# Programming_Interface_and_Power.net
KiCad netlist of a schematic drawn in Altium Designer
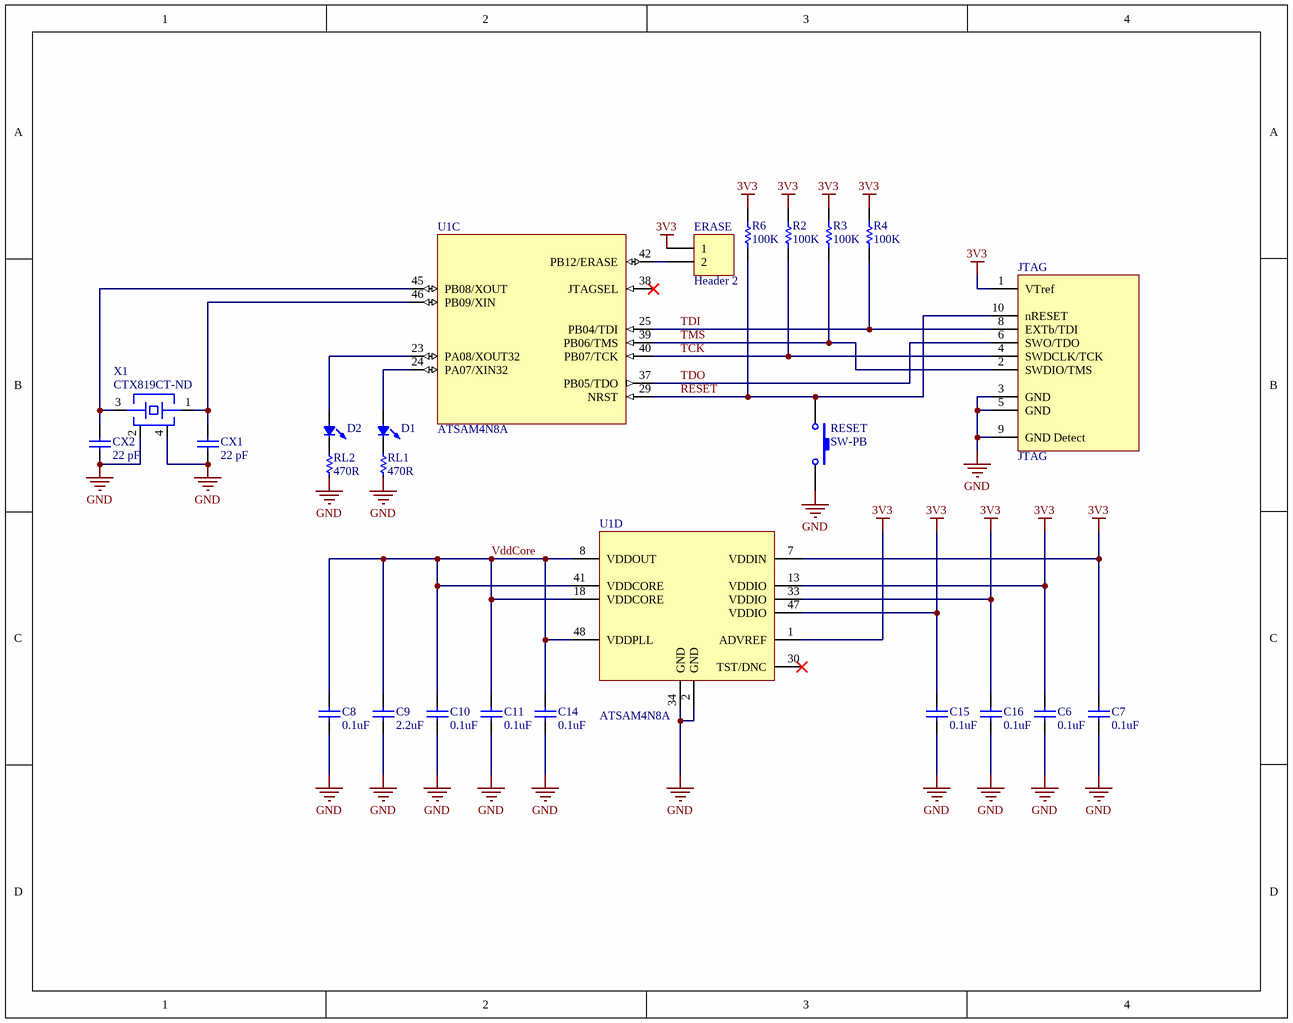
[diagram p0: Programming Interface and Power.SchDoc]

(export (version "E")
  (design (tool "Eeschema 10.0.6"))
  (components
    (comp (ref "C6")
      (value "0.1uF")
      (footprint "0603C")
      (description "Capacitor (Semiconductor SIM Model)")
      (fields (field (name "Comment") "Cap Semi") (field (name "PUBLISHER") "Altium Limited"))
      (libsource (lib "Miscellaneous Devices") (part "Cap Semi"))
    )
    (comp (ref "C7")
      (value "0.1uF")
      (footprint "0603C")
      (description "Capacitor (Semiconductor SIM Model)")
      (fields (field (name "Comment") "Cap Semi") (field (name "PUBLISHER") "Altium Limited"))
      (libsource (lib "Miscellaneous Devices") (part "Cap Semi"))
    )
    (comp (ref "C8")
      (value "0.1uF")
      (footprint "0603C")
      (description "Capacitor (Semiconductor SIM Model)")
      (fields (field (name "Comment") "Cap Semi") (field (name "PUBLISHER") "Altium Limited"))
      (libsource (lib "Miscellaneous Devices") (part "Cap Semi"))
    )
    (comp (ref "C9")
      (value "2.2uF")
      (footprint "1206C")
      (description "Capacitor (Semiconductor SIM Model)")
      (fields (field (name "Comment") "Cap Semi") (field (name "PUBLISHER") "Altium Limited"))
      (libsource (lib "Miscellaneous Devices") (part "Cap Semi"))
    )
    (comp (ref "C10")
      (value "0.1uF")
      (footprint "0603C")
      (description "Capacitor (Semiconductor SIM Model)")
      (fields (field (name "Comment") "Cap Semi") (field (name "PUBLISHER") "Altium Limited"))
      (libsource (lib "Miscellaneous Devices") (part "Cap Semi"))
    )
    (comp (ref "C11")
      (value "0.1uF")
      (footprint "0603C")
      (description "Capacitor (Semiconductor SIM Model)")
      (fields (field (name "Comment") "Cap Semi") (field (name "PUBLISHER") "Altium Limited"))
      (libsource (lib "Miscellaneous Devices") (part "Cap Semi"))
    )
    (comp (ref "C14")
      (value "0.1uF")
      (footprint "0603C")
      (description "Capacitor (Semiconductor SIM Model)")
      (fields (field (name "Comment") "Cap Semi") (field (name "PUBLISHER") "Altium Limited"))
      (libsource (lib "Miscellaneous Devices") (part "Cap Semi"))
    )
    (comp (ref "C15")
      (value "0.1uF")
      (footprint "0603C")
      (description "Capacitor (Semiconductor SIM Model)")
      (fields (field (name "Comment") "Cap Semi") (field (name "PUBLISHER") "Altium Limited"))
      (libsource (lib "Miscellaneous Devices") (part "Cap Semi"))
    )
    (comp (ref "C16")
      (value "0.1uF")
      (footprint "0603C")
      (description "Capacitor (Semiconductor SIM Model)")
      (fields (field (name "Comment") "Cap Semi") (field (name "PUBLISHER") "Altium Limited"))
      (libsource (lib "Miscellaneous Devices") (part "Cap Semi"))
    )
    (comp (ref "CX1")
      (value "22 pF")
      (footprint "0603C")
      (description "Capacitor (Semiconductor SIM Model)")
      (fields (field (name "Comment") "Cap Semi") (field (name "PUBLISHER") "Altium Limited"))
      (libsource (lib "Miscellaneous Devices") (part "Cap Semi"))
    )
    (comp (ref "CX2")
      (value "22 pF")
      (footprint "0603C")
      (description "Capacitor (Semiconductor SIM Model)")
      (fields (field (name "Comment") "Cap Semi") (field (name "PUBLISHER") "Altium Limited"))
      (libsource (lib "Miscellaneous Devices") (part "Cap Semi"))
    )
    (comp (ref "D1")
      (value "LED0")
      (footprint "0603 SMT LED")
      (description "T 1 3/4 LED")
      (fields (field (name "PUBLISHER") "Altium Limited"))
      (libsource (lib "Miscellaneous Devices") (part "LED0"))
    )
    (comp (ref "D2")
      (value "LED0")
      (footprint "0603 SMT LED")
      (description "T 1 3/4 LED")
      (fields (field (name "PUBLISHER") "Altium Limited"))
      (libsource (lib "Miscellaneous Devices") (part "LED0"))
    )
    (comp (ref "ERASE")
      (value "Header 2")
      (footprint "HDR1X2")
      (description "Header, 2-Pin")
      (fields (field (name "PUBLISHER") "Altium Limited"))
      (libsource (lib "Miscellaneous Connectors") (part "Header 2"))
    )
    (comp (ref "JTAG")
      (value "JTAG")
      (footprint "MHDR2X5 - Shrouded")
      (description "ARM 10-Pin JTAG Interface")
      (libsource (lib "Connectors") (part "ARM JTAG-10"))
    )
    (comp (ref "R2")
      (value "100K")
      (footprint "0603R")
      (description "Semiconductor Resistor")
      (fields (field (name "Comment") "Res Semi") (field (name "PUBLISHER") "Altium Limited"))
      (libsource (lib "Miscellaneous Devices") (part "Res Semi"))
    )
    (comp (ref "R3")
      (value "100K")
      (footprint "0603R")
      (description "Semiconductor Resistor")
      (fields (field (name "Comment") "Res Semi") (field (name "PUBLISHER") "Altium Limited"))
      (libsource (lib "Miscellaneous Devices") (part "Res Semi"))
    )
    (comp (ref "R4")
      (value "100K")
      (footprint "0603R")
      (description "Semiconductor Resistor")
      (fields (field (name "Comment") "Res Semi") (field (name "PUBLISHER") "Altium Limited"))
      (libsource (lib "Miscellaneous Devices") (part "Res Semi"))
    )
    (comp (ref "R6")
      (value "100K")
      (footprint "0603R")
      (description "Semiconductor Resistor")
      (fields (field (name "Comment") "Res Semi") (field (name "PUBLISHER") "Altium Limited"))
      (libsource (lib "Miscellaneous Devices") (part "Res Semi"))
    )
    (comp (ref "RESET")
      (value "SW-PB")
      (footprint "TL3302BF180QG/TR")
      (description "Switch")
      (fields (field (name "PUBLISHER") "Altium Limited"))
      (libsource (lib "Miscellaneous Devices") (part "SW-PB"))
    )
    (comp (ref "RL1")
      (value "470R")
      (footprint "0603R")
      (description "Semiconductor Resistor")
      (fields (field (name "Comment") "Res Semi Small") (field (name "PUBLISHER") "Altium Limited"))
      (libsource (lib "Miscellaneous Devices") (part "Res Semi Small"))
    )
    (comp (ref "RL2")
      (value "470R")
      (footprint "0603R")
      (description "Semiconductor Resistor")
      (fields (field (name "Comment") "Res Semi Small") (field (name "PUBLISHER") "Altium Limited"))
      (libsource (lib "Miscellaneous Devices") (part "Res Semi Small"))
    )
    (comp (ref "U1")
      (value "ATSAM4N8A")
      (footprint "TSQFP50P900X900-48N")
      (description "SAM4N ARM Cortex-M4 Microcontrollers")
      (libsource (lib "ICs") (part "ATSAM4N8A"))
    )
    (comp (ref "X1")
      (value "CTX819CT-ND")
      (footprint "Abracon ABM3B Crystal")
      (description "16 MHz Micro SMT Crystal")
      (libsource (lib "Unsorted") (part "SMT Crystal"))
    )
  )
  (nets
    (net (code "1") (name "/RESET") (class "Default")
      (node (ref "JTAG") (pin "10") (pinfunction "nRESET_10") (pintype "passive"))
      (node (ref "R6") (pin "1") (pinfunction "1_1") (pintype "passive"))
      (node (ref "RESET") (pin "1") (pinfunction "1_1") (pintype "passive"))
      (node (ref "U1") (pin "29") (pinfunction "NRST_29") (pintype "input"))
    )
    (net (code "2") (name "/TCK") (class "Default")
      (node (ref "JTAG") (pin "4") (pinfunction "SWDCLK/TCK_4") (pintype "passive"))
      (node (ref "R2") (pin "1") (pinfunction "1_1") (pintype "passive"))
      (node (ref "U1") (pin "40") (pinfunction "PB07/TCK_40") (pintype "input"))
    )
    (net (code "3") (name "/TDI") (class "Default")
      (node (ref "JTAG") (pin "8") (pinfunction "EXTb/TDI_8") (pintype "passive"))
      (node (ref "R4") (pin "1") (pinfunction "1_1") (pintype "passive"))
      (node (ref "U1") (pin "25") (pinfunction "PB04/TDI_25") (pintype "input"))
    )
    (net (code "4") (name "/TDO") (class "Default")
      (node (ref "JTAG") (pin "6") (pinfunction "SWO/TDO_6") (pintype "passive"))
      (node (ref "U1") (pin "37") (pinfunction "PB05/TDO_37") (pintype "output"))
    )
    (net (code "5") (name "/TMS") (class "Default")
      (node (ref "JTAG") (pin "2") (pinfunction "SWDIO/TMS_2") (pintype "passive"))
      (node (ref "R3") (pin "1") (pinfunction "1_1") (pintype "passive"))
      (node (ref "U1") (pin "39") (pinfunction "PB06/TMS_39") (pintype "input"))
    )
    (net (code "6") (name "/VddCore") (class "Default")
      (node (ref "C10") (pin "2") (pinfunction "2_2") (pintype "passive"))
      (node (ref "C11") (pin "2") (pinfunction "2_2") (pintype "passive"))
      (node (ref "C14") (pin "2") (pinfunction "2_2") (pintype "passive"))
      (node (ref "C8") (pin "2") (pinfunction "2_2") (pintype "passive"))
      (node (ref "C9") (pin "2") (pinfunction "2_2") (pintype "passive"))
      (node (ref "U1") (pin "18") (pinfunction "VDDCORE_18") (pintype "power_in"))
      (node (ref "U1") (pin "41") (pinfunction "VDDCORE_41") (pintype "power_in"))
      (node (ref "U1") (pin "48") (pinfunction "VDDPLL_48") (pintype "power_in"))
      (node (ref "U1") (pin "8") (pinfunction "VDDOUT_8") (pintype "power_in"))
    )
    (net (code "7") (name "3V3") (class "Default")
      (node (ref "C15") (pin "2") (pinfunction "2_2") (pintype "passive"))
      (node (ref "C16") (pin "2") (pinfunction "2_2") (pintype "passive"))
      (node (ref "C6") (pin "2") (pinfunction "2_2") (pintype "passive"))
      (node (ref "C7") (pin "2") (pinfunction "2_2") (pintype "passive"))
      (node (ref "ERASE") (pin "1") (pinfunction "1_1") (pintype "passive"))
      (node (ref "JTAG") (pin "1") (pinfunction "VTref_1") (pintype "passive"))
      (node (ref "R2") (pin "2") (pinfunction "2_2") (pintype "passive"))
      (node (ref "R3") (pin "2") (pinfunction "2_2") (pintype "passive"))
      (node (ref "R4") (pin "2") (pinfunction "2_2") (pintype "passive"))
      (node (ref "R6") (pin "2") (pinfunction "2_2") (pintype "passive"))
      (node (ref "U1") (pin "1") (pinfunction "ADVREF_1") (pintype "power_in"))
      (node (ref "U1") (pin "13") (pinfunction "VDDIO_13") (pintype "power_in"))
      (node (ref "U1") (pin "33") (pinfunction "VDDIO_33") (pintype "power_in"))
      (node (ref "U1") (pin "47") (pinfunction "VDDIO_47") (pintype "power_in"))
      (node (ref "U1") (pin "7") (pinfunction "VDDIN_7") (pintype "power_in"))
    )
    (net (code "8") (name "GND") (class "Default")
      (node (ref "C10") (pin "1") (pinfunction "1_1") (pintype "passive"))
      (node (ref "C11") (pin "1") (pinfunction "1_1") (pintype "passive"))
      (node (ref "C14") (pin "1") (pinfunction "1_1") (pintype "passive"))
      (node (ref "C15") (pin "1") (pinfunction "1_1") (pintype "passive"))
      (node (ref "C16") (pin "1") (pinfunction "1_1") (pintype "passive"))
      (node (ref "C6") (pin "1") (pinfunction "1_1") (pintype "passive"))
      (node (ref "C7") (pin "1") (pinfunction "1_1") (pintype "passive"))
      (node (ref "C8") (pin "1") (pinfunction "1_1") (pintype "passive"))
      (node (ref "C9") (pin "1") (pinfunction "1_1") (pintype "passive"))
      (node (ref "CX1") (pin "1") (pinfunction "1_1") (pintype "passive"))
      (node (ref "CX2") (pin "1") (pinfunction "1_1") (pintype "passive"))
      (node (ref "JTAG") (pin "3") (pinfunction "GND_3") (pintype "power_in"))
      (node (ref "JTAG") (pin "5") (pinfunction "GND_5") (pintype "power_in"))
      (node (ref "JTAG") (pin "9") (pinfunction "GND_Detect_9") (pintype "passive"))
      (node (ref "RESET") (pin "2") (pinfunction "2_2") (pintype "passive"))
      (node (ref "RL1") (pin "2") (pinfunction "2_2") (pintype "passive"))
      (node (ref "RL2") (pin "2") (pinfunction "2_2") (pintype "passive"))
      (node (ref "U1") (pin "2") (pinfunction "GND_2") (pintype "power_in"))
      (node (ref "U1") (pin "34") (pinfunction "GND_34") (pintype "power_in"))
      (node (ref "X1") (pin "2") (pinfunction "2_2") (pintype "passive"))
      (node (ref "X1") (pin "4") (pinfunction "4_4") (pintype "passive"))
    )
    (net (code "9") (name "Net-(D1-Pad2)") (class "Default")
      (node (ref "D1") (pin "2") (pinfunction "2_2") (pintype "passive"))
      (node (ref "RL1") (pin "1") (pinfunction "1_1") (pintype "passive"))
    )
    (net (code "10") (name "Net-(D2-Pad2)") (class "Default")
      (node (ref "D2") (pin "2") (pinfunction "2_2") (pintype "passive"))
      (node (ref "RL2") (pin "1") (pinfunction "1_1") (pintype "passive"))
    )
    (net (code "11") (name "Net-(U1C-PA07{slash}XIN32)") (class "Default")
      (node (ref "D1") (pin "1") (pinfunction "1_1") (pintype "passive"))
      (node (ref "U1") (pin "24") (pinfunction "PA07/XIN32_24") (pintype "bidirectional"))
    )
    (net (code "12") (name "Net-(U1C-PA08{slash}XOUT32)") (class "Default")
      (node (ref "D2") (pin "1") (pinfunction "1_1") (pintype "passive"))
      (node (ref "U1") (pin "23") (pinfunction "PA08/XOUT32_23") (pintype "bidirectional"))
    )
    (net (code "13") (name "Net-(U1C-PB08{slash}XOUT)") (class "Default")
      (node (ref "CX2") (pin "2") (pinfunction "2_2") (pintype "passive"))
      (node (ref "U1") (pin "45") (pinfunction "PB08/XOUT_45") (pintype "bidirectional"))
      (node (ref "X1") (pin "3") (pinfunction "3_3") (pintype "passive"))
    )
    (net (code "14") (name "Net-(U1C-PB09{slash}XIN)") (class "Default")
      (node (ref "CX1") (pin "2") (pinfunction "2_2") (pintype "passive"))
      (node (ref "U1") (pin "46") (pinfunction "PB09/XIN_46") (pintype "bidirectional"))
      (node (ref "X1") (pin "1") (pinfunction "1_1") (pintype "passive"))
    )
    (net (code "15") (name "Net-(U1C-PB12{slash}ERASE)") (class "Default")
      (node (ref "ERASE") (pin "2") (pinfunction "2_2") (pintype "passive"))
      (node (ref "U1") (pin "42") (pinfunction "PB12/ERASE_42") (pintype "bidirectional"))
    )
    (net (code "16") (name "unconnected-(U1C-JTAGSEL-Pad38)") (class "Default")
      (node (ref "U1") (pin "38") (pinfunction "JTAGSEL_38") (pintype "input+no_connect"))
    )
    (net (code "17") (name "unconnected-(U1D-TST{slash}DNC-Pad30)") (class "Default")
      (node (ref "U1") (pin "30") (pinfunction "TST/DNC_30") (pintype "passive+no_connect"))
    )
  )
)
